# flightcontroller.net
KiCad netlist of a schematic drawn in EAGLE
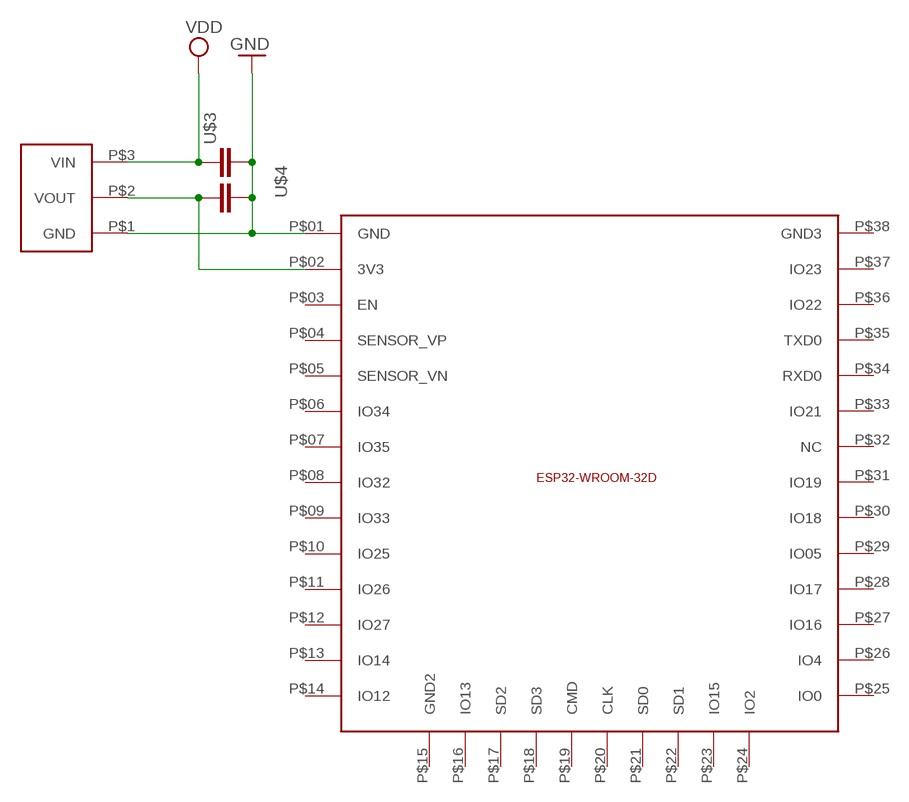
[diagram p0: schematic, sheet 1]

(export (version "E")
  (design (tool "Eeschema 10.0.6"))
  (components
    (comp (ref "U$1")
      (value "ESP32")
      (footprint "eagle-import:ESP32-WROOM-32D")
      (libsource (lib "eagle-import") (part "ESP32"))
    )
    (comp (ref "U$2")
      (value "REG1117")
      (footprint "eagle-import:REG1117")
      (libsource (lib "eagle-import") (part "REG1117"))
    )
    (comp (ref "U$3")
      (value "C_TANTALUM-1411(3528-METRIC)")
      (footprint "eagle-import:CAPM3528X210")
      (libsource (lib "eagle-import") (part "CTANTALUM-1411(3528-METRIC)_"))
    )
    (comp (ref "U$4")
      (value "C_TANTALUM-1411(3528-METRIC)")
      (footprint "eagle-import:CAPM3528X210")
      (libsource (lib "eagle-import") (part "CTANTALUM-1411(3528-METRIC)_"))
    )
  )
  (nets
    (net (code "1") (name "GND") (class "Default")
      (node (ref "U$1") (pin "P$01") (pinfunction "GND_P$01") (pintype "bidirectional"))
      (node (ref "U$2") (pin "P$1") (pinfunction "GND_P$1") (pintype "bidirectional"))
      (node (ref "U$3") (pin "2") (pinfunction "2_2") (pintype "passive"))
      (node (ref "U$4") (pin "2") (pinfunction "2_2") (pintype "passive"))
    )
    (net (code "2") (name "Net-(U$1-3V3)") (class "Default")
      (node (ref "U$1") (pin "P$02") (pinfunction "3V3_P$02") (pintype "bidirectional"))
      (node (ref "U$2") (pin "P$2") (pinfunction "VOUT_P$2") (pintype "bidirectional"))
      (node (ref "U$4") (pin "1") (pinfunction "1_1") (pintype "passive"))
    )
    (net (code "3") (name "VDD") (class "Default")
      (node (ref "U$2") (pin "P$3") (pinfunction "VIN_P$3") (pintype "bidirectional"))
      (node (ref "U$3") (pin "1") (pinfunction "1_1") (pintype "passive"))
    )
    (net (code "4") (name "unconnected-(U$1-CLK-PadP$20)") (class "Default")
      (node (ref "U$1") (pin "P$20") (pinfunction "CLK_P$20") (pintype "bidirectional"))
    )
    (net (code "5") (name "unconnected-(U$1-CMD-PadP$19)") (class "Default")
      (node (ref "U$1") (pin "P$19") (pinfunction "CMD_P$19") (pintype "bidirectional"))
    )
    (net (code "6") (name "unconnected-(U$1-EN-PadP$03)") (class "Default")
      (node (ref "U$1") (pin "P$03") (pinfunction "EN_P$03") (pintype "bidirectional"))
    )
    (net (code "7") (name "unconnected-(U$1-GND2-PadP$15)") (class "Default")
      (node (ref "U$1") (pin "P$15") (pinfunction "GND2_P$15") (pintype "bidirectional"))
    )
    (net (code "8") (name "unconnected-(U$1-GND3-PadP$38)") (class "Default")
      (node (ref "U$1") (pin "P$38") (pinfunction "GND3_P$38") (pintype "bidirectional"))
    )
    (net (code "9") (name "unconnected-(U$1-IO0-PadP$25)") (class "Default")
      (node (ref "U$1") (pin "P$25") (pinfunction "IO0_P$25") (pintype "bidirectional"))
    )
    (net (code "10") (name "unconnected-(U$1-IO2-PadP$24)") (class "Default")
      (node (ref "U$1") (pin "P$24") (pinfunction "IO2_P$24") (pintype "bidirectional"))
    )
    (net (code "11") (name "unconnected-(U$1-IO4-PadP$26)") (class "Default")
      (node (ref "U$1") (pin "P$26") (pinfunction "IO4_P$26") (pintype "bidirectional"))
    )
    (net (code "12") (name "unconnected-(U$1-IO05-PadP$29)") (class "Default")
      (node (ref "U$1") (pin "P$29") (pinfunction "IO05_P$29") (pintype "bidirectional"))
    )
    (net (code "13") (name "unconnected-(U$1-IO12-PadP$14)") (class "Default")
      (node (ref "U$1") (pin "P$14") (pinfunction "IO12_P$14") (pintype "bidirectional"))
    )
    (net (code "14") (name "unconnected-(U$1-IO13-PadP$16)") (class "Default")
      (node (ref "U$1") (pin "P$16") (pinfunction "IO13_P$16") (pintype "bidirectional"))
    )
    (net (code "15") (name "unconnected-(U$1-IO14-PadP$13)") (class "Default")
      (node (ref "U$1") (pin "P$13") (pinfunction "IO14_P$13") (pintype "bidirectional"))
    )
    (net (code "16") (name "unconnected-(U$1-IO15-PadP$23)") (class "Default")
      (node (ref "U$1") (pin "P$23") (pinfunction "IO15_P$23") (pintype "bidirectional"))
    )
    (net (code "17") (name "unconnected-(U$1-IO16-PadP$27)") (class "Default")
      (node (ref "U$1") (pin "P$27") (pinfunction "IO16_P$27") (pintype "bidirectional"))
    )
    (net (code "18") (name "unconnected-(U$1-IO17-PadP$28)") (class "Default")
      (node (ref "U$1") (pin "P$28") (pinfunction "IO17_P$28") (pintype "bidirectional"))
    )
    (net (code "19") (name "unconnected-(U$1-IO18-PadP$30)") (class "Default")
      (node (ref "U$1") (pin "P$30") (pinfunction "IO18_P$30") (pintype "bidirectional"))
    )
    (net (code "20") (name "unconnected-(U$1-IO19-PadP$31)") (class "Default")
      (node (ref "U$1") (pin "P$31") (pinfunction "IO19_P$31") (pintype "bidirectional"))
    )
    (net (code "21") (name "unconnected-(U$1-IO21-PadP$33)") (class "Default")
      (node (ref "U$1") (pin "P$33") (pinfunction "IO21_P$33") (pintype "bidirectional"))
    )
    (net (code "22") (name "unconnected-(U$1-IO22-PadP$36)") (class "Default")
      (node (ref "U$1") (pin "P$36") (pinfunction "IO22_P$36") (pintype "bidirectional"))
    )
    (net (code "23") (name "unconnected-(U$1-IO23-PadP$37)") (class "Default")
      (node (ref "U$1") (pin "P$37") (pinfunction "IO23_P$37") (pintype "bidirectional"))
    )
    (net (code "24") (name "unconnected-(U$1-IO25-PadP$10)") (class "Default")
      (node (ref "U$1") (pin "P$10") (pinfunction "IO25_P$10") (pintype "bidirectional"))
    )
    (net (code "25") (name "unconnected-(U$1-IO26-PadP$11)") (class "Default")
      (node (ref "U$1") (pin "P$11") (pinfunction "IO26_P$11") (pintype "bidirectional"))
    )
    (net (code "26") (name "unconnected-(U$1-IO27-PadP$12)") (class "Default")
      (node (ref "U$1") (pin "P$12") (pinfunction "IO27_P$12") (pintype "bidirectional"))
    )
    (net (code "27") (name "unconnected-(U$1-IO32-PadP$08)") (class "Default")
      (node (ref "U$1") (pin "P$08") (pinfunction "IO32_P$08") (pintype "bidirectional"))
    )
    (net (code "28") (name "unconnected-(U$1-IO33-PadP$09)") (class "Default")
      (node (ref "U$1") (pin "P$09") (pinfunction "IO33_P$09") (pintype "bidirectional"))
    )
    (net (code "29") (name "unconnected-(U$1-IO34-PadP$06)") (class "Default")
      (node (ref "U$1") (pin "P$06") (pinfunction "IO34_P$06") (pintype "bidirectional"))
    )
    (net (code "30") (name "unconnected-(U$1-IO35-PadP$07)") (class "Default")
      (node (ref "U$1") (pin "P$07") (pinfunction "IO35_P$07") (pintype "bidirectional"))
    )
    (net (code "31") (name "unconnected-(U$1-NC-PadP$32)") (class "Default")
      (node (ref "U$1") (pin "P$32") (pinfunction "NC_P$32") (pintype "bidirectional"))
    )
    (net (code "32") (name "unconnected-(U$1-RXD0-PadP$34)") (class "Default")
      (node (ref "U$1") (pin "P$34") (pinfunction "RXD0_P$34") (pintype "bidirectional"))
    )
    (net (code "33") (name "unconnected-(U$1-SD0-PadP$21)") (class "Default")
      (node (ref "U$1") (pin "P$21") (pinfunction "SD0_P$21") (pintype "bidirectional"))
    )
    (net (code "34") (name "unconnected-(U$1-SD1-PadP$22)") (class "Default")
      (node (ref "U$1") (pin "P$22") (pinfunction "SD1_P$22") (pintype "bidirectional"))
    )
    (net (code "35") (name "unconnected-(U$1-SD2-PadP$17)") (class "Default")
      (node (ref "U$1") (pin "P$17") (pinfunction "SD2_P$17") (pintype "bidirectional"))
    )
    (net (code "36") (name "unconnected-(U$1-SD3-PadP$18)") (class "Default")
      (node (ref "U$1") (pin "P$18") (pinfunction "SD3_P$18") (pintype "bidirectional"))
    )
    (net (code "37") (name "unconnected-(U$1-SENSOR_VN-PadP$05)") (class "Default")
      (node (ref "U$1") (pin "P$05") (pinfunction "SENSOR_VN_P$05") (pintype "bidirectional"))
    )
    (net (code "38") (name "unconnected-(U$1-SENSOR_VP-PadP$04)") (class "Default")
      (node (ref "U$1") (pin "P$04") (pinfunction "SENSOR_VP_P$04") (pintype "bidirectional"))
    )
    (net (code "39") (name "unconnected-(U$1-TXD0-PadP$35)") (class "Default")
      (node (ref "U$1") (pin "P$35") (pinfunction "TXD0_P$35") (pintype "bidirectional"))
    )
  )
)
